# Battery_Voltaege_Sense.net
KiCad netlist of a schematic drawn in Altium Designer
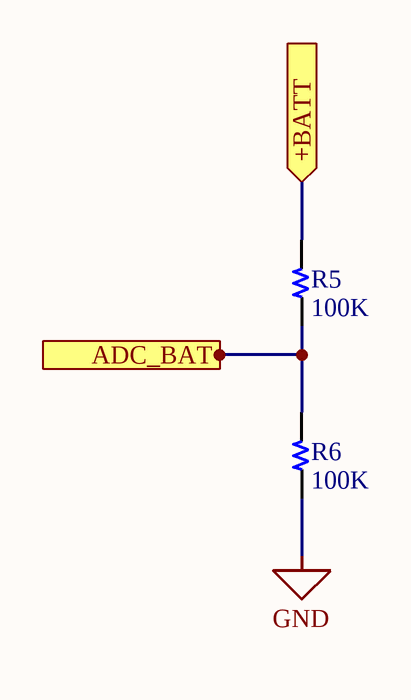
[diagram p0: Battery Voltaege Sense.SchDoc]

(export (version "E")
  (design (tool "Eeschema 10.0.6"))
  (components
    (comp (ref "R5")
      (value "100K")
      (footprint "R 0805")
      (description "Resistor")
      (libsource (lib "chipfc_libs") (part "Resistor"))
    )
    (comp (ref "R6")
      (value "100K")
      (footprint "R 0805")
      (description "Resistor")
      (libsource (lib "chipfc_libs") (part "Resistor"))
    )
  )
  (nets
    (net (code "1") (name "/+BATT") (class "Default")
      (node (ref "R5") (pin "2") (pinfunction "2_2") (pintype "passive"))
    )
    (net (code "2") (name "/ADC_BAT") (class "Default")
      (node (ref "R5") (pin "1") (pinfunction "1_1") (pintype "passive"))
      (node (ref "R6") (pin "2") (pinfunction "2_2") (pintype "passive"))
    )
    (net (code "3") (name "GND") (class "Default")
      (node (ref "R6") (pin "1") (pinfunction "1_1") (pintype "passive"))
    )
  )
)
